# sfpp_conn.net
KiCad netlist of a schematic drawn in Altium Designer
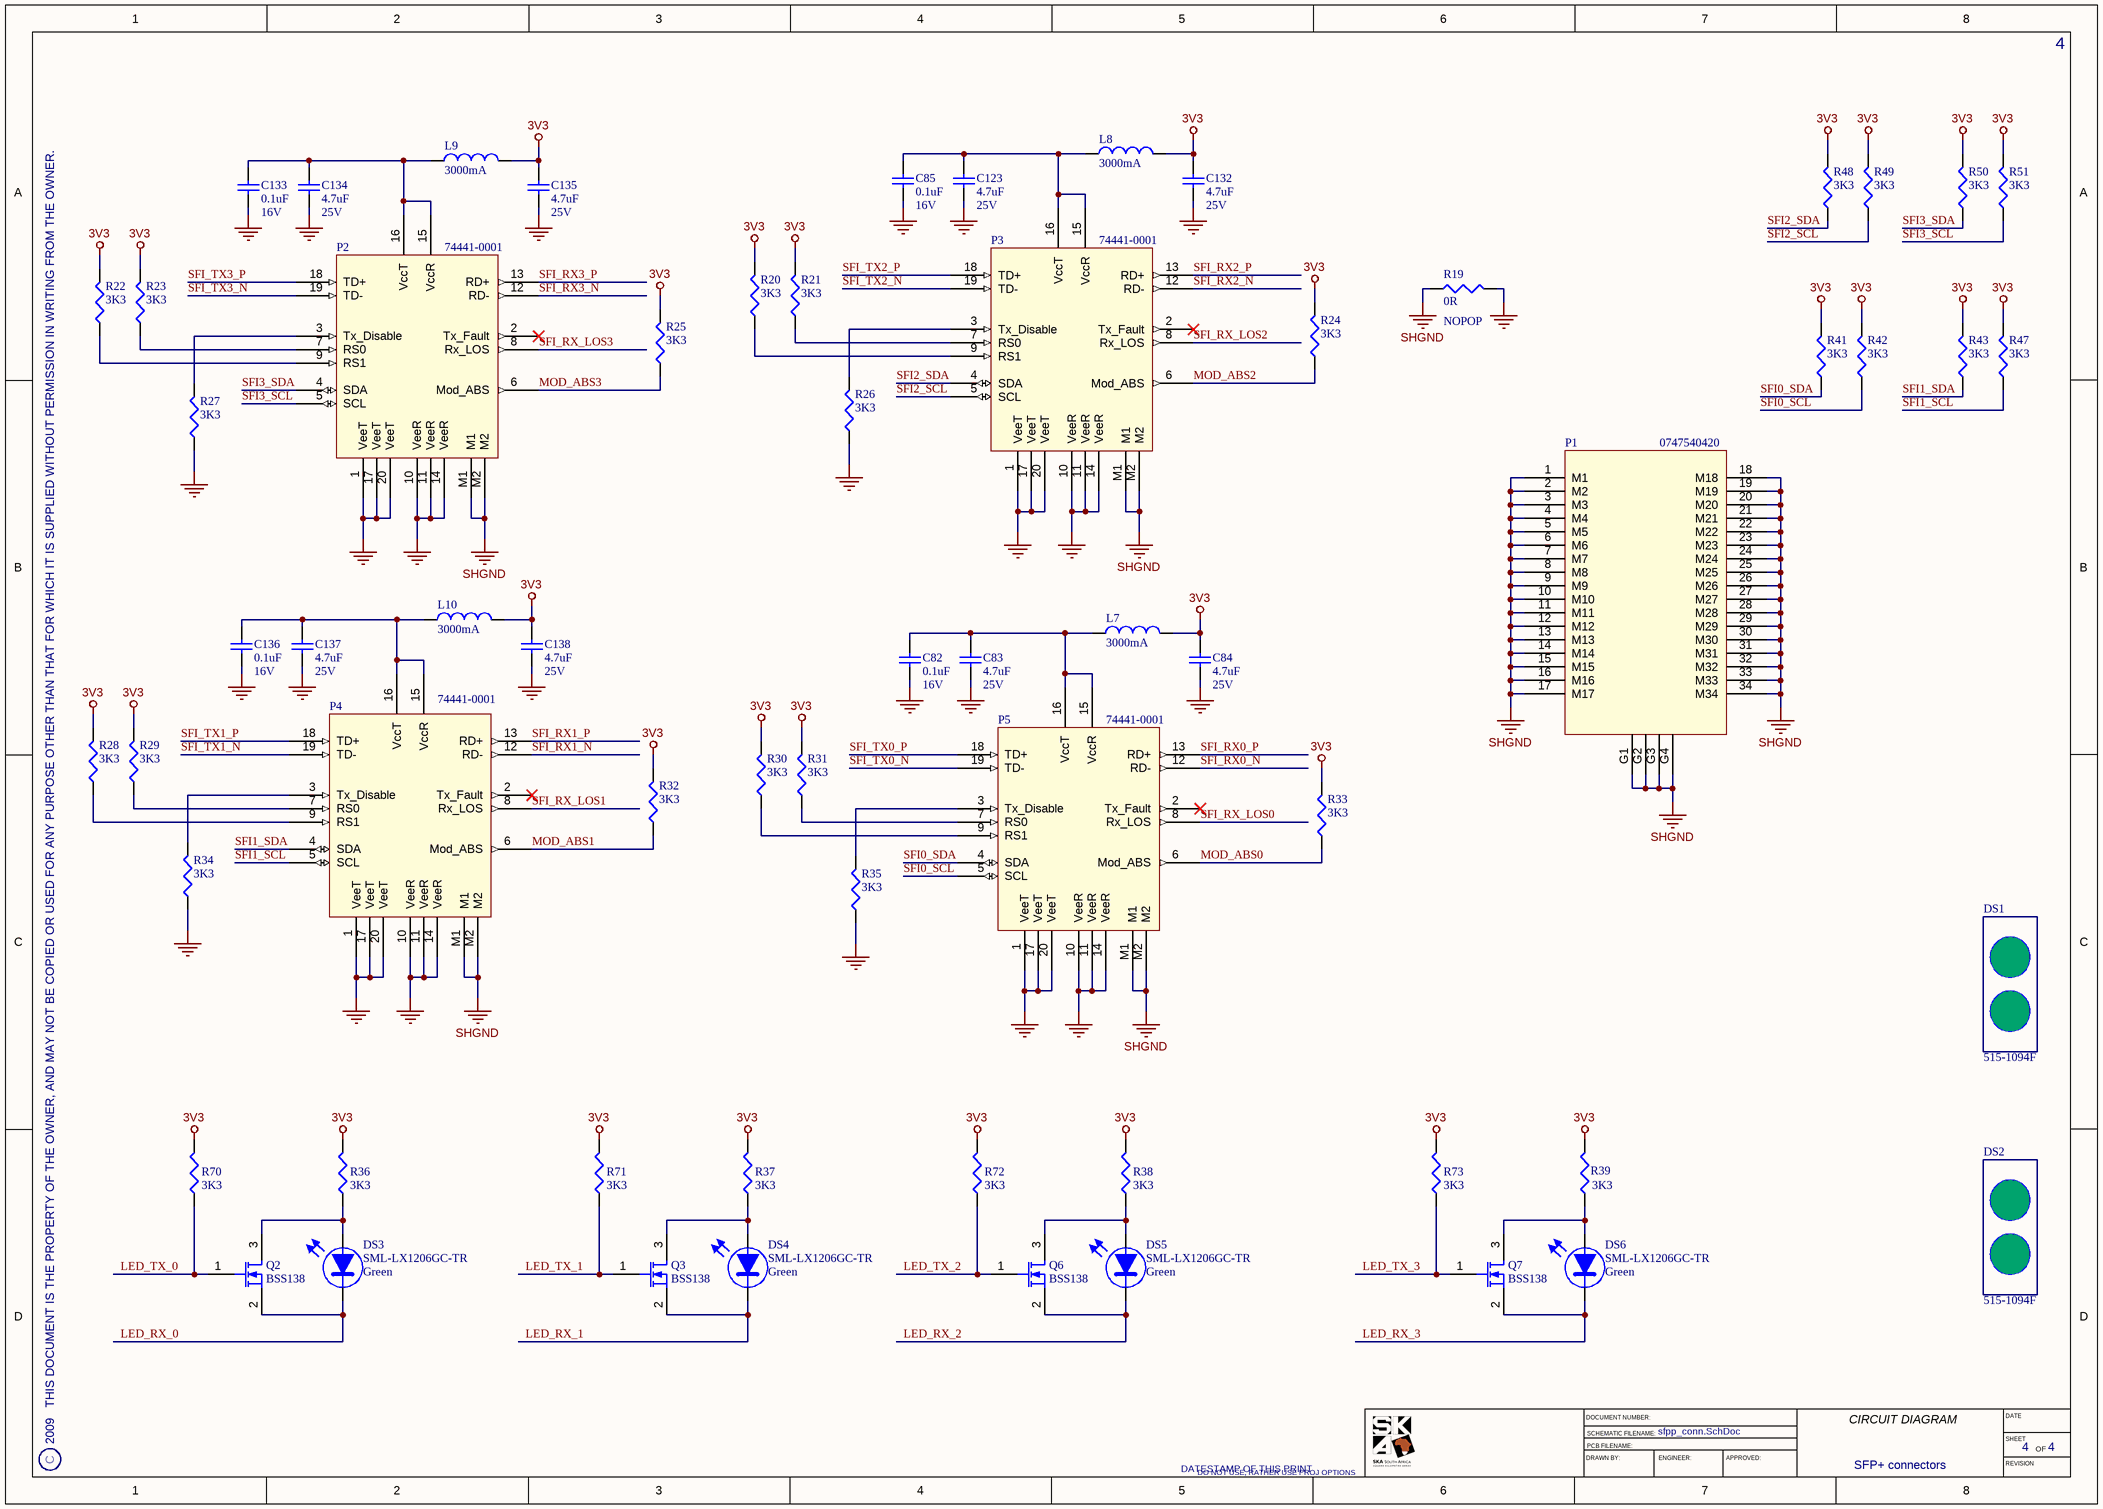
[diagram p0: sfpp_conn.SchDoc]

(export (version "E")
  (design (tool "Eeschema 10.0.6"))
  (components
    (comp (ref "C82")
      (value "0.1uF")
      (footprint "CAPC1005X60L")
      (description "0.1uF, Ceramic Capacitor")
      (fields
        (field (name "RATING") "16V")
        (field (name "MANUFACTURER") "VENKEL")
        (field (name "PARTNUM") "C0402X7R160-104KN")
      )
      (libsource (lib "altium_db") (part "CapStd"))
    )
    (comp (ref "C83")
      (value "4.7uF")
      (footprint "CAPC2012X127L")
      (description "4.7uF, Ceramic Capacitor")
      (fields
        (field (name "RATING") "25V")
        (field (name "MANUFACTURER") "MURATA")
        (field (name "PARTNUM") "GRM21BR61E475KA12K")
      )
      (libsource (lib "altium_db") (part "CapStd"))
    )
    (comp (ref "C84")
      (value "4.7uF")
      (footprint "CAPC2012X127L")
      (description "4.7uF, Ceramic Capacitor")
      (fields
        (field (name "RATING") "25V")
        (field (name "MANUFACTURER") "MURATA")
        (field (name "PARTNUM") "GRM21BR61E475KA12K")
      )
      (libsource (lib "altium_db") (part "CapStd"))
    )
    (comp (ref "C85")
      (value "0.1uF")
      (footprint "CAPC1005X60L")
      (description "0.1uF, Ceramic Capacitor")
      (fields
        (field (name "RATING") "16V")
        (field (name "MANUFACTURER") "VENKEL")
        (field (name "PARTNUM") "C0402X7R160-104KN")
      )
      (libsource (lib "altium_db") (part "CapStd"))
    )
    (comp (ref "C123")
      (value "4.7uF")
      (footprint "CAPC2012X127L")
      (description "4.7uF, Ceramic Capacitor")
      (fields
        (field (name "RATING") "25V")
        (field (name "MANUFACTURER") "MURATA")
        (field (name "PARTNUM") "GRM21BR61E475KA12K")
      )
      (libsource (lib "altium_db") (part "CapStd"))
    )
    (comp (ref "C132")
      (value "4.7uF")
      (footprint "CAPC2012X127L")
      (description "4.7uF, Ceramic Capacitor")
      (fields
        (field (name "RATING") "25V")
        (field (name "MANUFACTURER") "MURATA")
        (field (name "PARTNUM") "GRM21BR61E475KA12K")
      )
      (libsource (lib "altium_db") (part "CapStd"))
    )
    (comp (ref "C133")
      (value "0.1uF")
      (footprint "CAPC1005X60L")
      (description "0.1uF, Ceramic Capacitor")
      (fields
        (field (name "RATING") "16V")
        (field (name "MANUFACTURER") "VENKEL")
        (field (name "PARTNUM") "C0402X7R160-104KN")
      )
      (libsource (lib "altium_db") (part "CapStd"))
    )
    (comp (ref "C134")
      (value "4.7uF")
      (footprint "CAPC2012X127L")
      (description "4.7uF, Ceramic Capacitor")
      (fields
        (field (name "RATING") "25V")
        (field (name "MANUFACTURER") "MURATA")
        (field (name "PARTNUM") "GRM21BR61E475KA12K")
      )
      (libsource (lib "altium_db") (part "CapStd"))
    )
    (comp (ref "C135")
      (value "4.7uF")
      (footprint "CAPC2012X127L")
      (description "4.7uF, Ceramic Capacitor")
      (fields
        (field (name "RATING") "25V")
        (field (name "MANUFACTURER") "MURATA")
        (field (name "PARTNUM") "GRM21BR61E475KA12K")
      )
      (libsource (lib "altium_db") (part "CapStd"))
    )
    (comp (ref "C136")
      (value "0.1uF")
      (footprint "CAPC1005X60L")
      (description "0.1uF, Ceramic Capacitor")
      (fields
        (field (name "RATING") "16V")
        (field (name "MANUFACTURER") "VENKEL")
        (field (name "PARTNUM") "C0402X7R160-104KN")
      )
      (libsource (lib "altium_db") (part "CapStd"))
    )
    (comp (ref "C137")
      (value "4.7uF")
      (footprint "CAPC2012X127L")
      (description "4.7uF, Ceramic Capacitor")
      (fields
        (field (name "RATING") "25V")
        (field (name "MANUFACTURER") "MURATA")
        (field (name "PARTNUM") "GRM21BR61E475KA12K")
      )
      (libsource (lib "altium_db") (part "CapStd"))
    )
    (comp (ref "C138")
      (value "4.7uF")
      (footprint "CAPC2012X127L")
      (description "4.7uF, Ceramic Capacitor")
      (fields
        (field (name "RATING") "25V")
        (field (name "MANUFACTURER") "MURATA")
        (field (name "PARTNUM") "GRM21BR61E475KA12K")
      )
      (libsource (lib "altium_db") (part "CapStd"))
    )
    (comp (ref "DS1")
      (value "515-1094F")
      (footprint "DIALIGHT_515-1094F")
      (description "2-High, press-fit, 3mm round, light-pipe")
      (fields (field (name "MANUFACTURER") "Dialight"))
      (libsource (lib "altium_db") (part "LPIPE_2H"))
    )
    (comp (ref "DS2")
      (value "515-1094F")
      (footprint "DIALIGHT_515-1094F")
      (description "2-High, press-fit, 3mm round, light-pipe")
      (fields (field (name "MANUFACTURER") "Dialight"))
      (libsource (lib "altium_db") (part "LPIPE_2H"))
    )
    (comp (ref "DS3")
      (value "SML-LX1206GC-TR")
      (footprint "LEDC3216X120N")
      (description "Green, Surface mount, LED, 1206")
      (fields (field (name "COLOUR") "Green") (field (name "MANUFACTURER") "LUMEX"))
      (libsource (lib "altium_db") (part "LEDSTD"))
    )
    (comp (ref "DS4")
      (value "SML-LX1206GC-TR")
      (footprint "LEDC3216X120N")
      (description "Green, Surface mount, LED, 1206")
      (fields (field (name "COLOUR") "Green") (field (name "MANUFACTURER") "LUMEX"))
      (libsource (lib "altium_db") (part "LEDSTD"))
    )
    (comp (ref "DS5")
      (value "SML-LX1206GC-TR")
      (footprint "LEDC3216X120N")
      (description "Green, Surface mount, LED, 1206")
      (fields (field (name "COLOUR") "Green") (field (name "MANUFACTURER") "LUMEX"))
      (libsource (lib "altium_db") (part "LEDSTD"))
    )
    (comp (ref "DS6")
      (value "SML-LX1206GC-TR")
      (footprint "LEDC3216X120N")
      (description "Green, Surface mount, LED, 1206")
      (fields (field (name "COLOUR") "Green") (field (name "MANUFACTURER") "LUMEX"))
      (libsource (lib "altium_db") (part "LEDSTD"))
    )
    (comp (ref "L7")
      (value "120R")
      (footprint "INDC3216X130L")
      (description "120 Ohm, Chip Ferrite Brad")
      (fields
        (field (name "RATING") "3000mA")
        (field (name "MANUFACTURER") "Murata")
        (field (name "PARTNUM") "BLM31PG121SN1")
      )
      (libsource (lib "altium_db") (part "IndStd"))
    )
    (comp (ref "L8")
      (value "120R")
      (footprint "INDC3216X130L")
      (description "120 Ohm, Chip Ferrite Brad")
      (fields
        (field (name "RATING") "3000mA")
        (field (name "MANUFACTURER") "Murata")
        (field (name "PARTNUM") "BLM31PG121SN1")
      )
      (libsource (lib "altium_db") (part "IndStd"))
    )
    (comp (ref "L9")
      (value "120R")
      (footprint "INDC3216X130L")
      (description "120 Ohm, Chip Ferrite Brad")
      (fields
        (field (name "RATING") "3000mA")
        (field (name "MANUFACTURER") "Murata")
        (field (name "PARTNUM") "BLM31PG121SN1")
      )
      (libsource (lib "altium_db") (part "IndStd"))
    )
    (comp (ref "L10")
      (value "120R")
      (footprint "INDC3216X130L")
      (description "120 Ohm, Chip Ferrite Brad")
      (fields
        (field (name "RATING") "3000mA")
        (field (name "MANUFACTURER") "Murata")
        (field (name "PARTNUM") "BLM31PG121SN1")
      )
      (libsource (lib "altium_db") (part "IndStd"))
    )
    (comp (ref "P1")
      (value "0747540420")
      (footprint "MOLEX_0747540420")
      (description "SFP+ 1X4 Cage Assembly")
      (fields (field (name "PARTNUM") "0747540420") (field (name "MANUFACTURER") "Molex"))
      (libsource (lib "altium_db") (part "MOLEX_0747540420"))
    )
    (comp (ref "P2")
      (value "74441-0001")
      (footprint "MOLEX_74441-0001")
      (description "20 Circuit, 0.8mm pitch SFP+ host connector")
      (fields (field (name "PARTNUM") "74441-0001") (field (name "MANUFACTURER") "Molex"))
      (libsource (lib "altium_db") (part "MOLEX_74441-0001"))
    )
    (comp (ref "P3")
      (value "74441-0001")
      (footprint "MOLEX_74441-0001")
      (description "20 Circuit, 0.8mm pitch SFP+ host connector")
      (fields (field (name "PARTNUM") "74441-0001") (field (name "MANUFACTURER") "Molex"))
      (libsource (lib "altium_db") (part "MOLEX_74441-0001"))
    )
    (comp (ref "P4")
      (value "74441-0001")
      (footprint "MOLEX_74441-0001")
      (description "20 Circuit, 0.8mm pitch SFP+ host connector")
      (fields (field (name "PARTNUM") "74441-0001") (field (name "MANUFACTURER") "Molex"))
      (libsource (lib "altium_db") (part "MOLEX_74441-0001"))
    )
    (comp (ref "P5")
      (value "74441-0001")
      (footprint "MOLEX_74441-0001")
      (description "20 Circuit, 0.8mm pitch SFP+ host connector")
      (fields (field (name "PARTNUM") "74441-0001") (field (name "MANUFACTURER") "Molex"))
      (libsource (lib "altium_db") (part "MOLEX_74441-0001"))
    )
    (comp (ref "Q2")
      (value "BSS138")
      (footprint "SOT95P245X110-3N")
      (description "N-Channel Logic Level Enhancement Mode Field Effect Transistor")
      (fields (field (name "MANUFACTURER") "Fairchild Semiconductor"))
      (libsource (lib "Altium_DB") (part "BSS138"))
    )
    (comp (ref "Q3")
      (value "BSS138")
      (footprint "SOT95P245X110-3N")
      (description "N-Channel Logic Level Enhancement Mode Field Effect Transistor")
      (fields (field (name "MANUFACTURER") "Fairchild Semiconductor"))
      (libsource (lib "Altium_DB") (part "BSS138"))
    )
    (comp (ref "Q6")
      (value "BSS138")
      (footprint "SOT95P245X110-3N")
      (description "N-Channel Logic Level Enhancement Mode Field Effect Transistor")
      (fields (field (name "MANUFACTURER") "Fairchild Semiconductor"))
      (libsource (lib "Altium_DB") (part "BSS138"))
    )
    (comp (ref "Q7")
      (value "BSS138")
      (footprint "SOT95P245X110-3N")
      (description "N-Channel Logic Level Enhancement Mode Field Effect Transistor")
      (fields (field (name "MANUFACTURER") "Fairchild Semiconductor"))
      (libsource (lib "Altium_DB") (part "BSS138"))
    )
    (comp (ref "R19")
      (value "0R")
      (footprint "RESC1005X40L")
      (description "0R, 1.1mm x 0.5mm, Thick Film Resistor")
      (fields (field (name "MANUFACTURER") "ROYALOHM") (field (name "PARTNUM") "0402WG00000T1E"))
      (libsource (lib "altium_db") (part "ResStd"))
    )
    (comp (ref "R20")
      (value "3K3")
      (footprint "RESC1005X40L")
      (description "3K3, 1.1mm x 0.5mm, Thick Film Resistor")
      (fields (field (name "MANUFACTURER") "ROYALOHM") (field (name "PARTNUM") "0402WGJ0332T1E"))
      (libsource (lib "altium_db") (part "ResStd"))
    )
    (comp (ref "R21")
      (value "3K3")
      (footprint "RESC1005X40L")
      (description "3K3, 1.1mm x 0.5mm, Thick Film Resistor")
      (fields (field (name "MANUFACTURER") "ROYALOHM") (field (name "PARTNUM") "0402WGJ0332T1E"))
      (libsource (lib "altium_db") (part "ResStd"))
    )
    (comp (ref "R22")
      (value "3K3")
      (footprint "RESC1005X40L")
      (description "3K3, 1.1mm x 0.5mm, Thick Film Resistor")
      (fields (field (name "MANUFACTURER") "ROYALOHM") (field (name "PARTNUM") "0402WGJ0332T1E"))
      (libsource (lib "altium_db") (part "ResStd"))
    )
    (comp (ref "R23")
      (value "3K3")
      (footprint "RESC1005X40L")
      (description "3K3, 1.1mm x 0.5mm, Thick Film Resistor")
      (fields (field (name "MANUFACTURER") "ROYALOHM") (field (name "PARTNUM") "0402WGJ0332T1E"))
      (libsource (lib "altium_db") (part "ResStd"))
    )
    (comp (ref "R24")
      (value "3K3")
      (footprint "RESC1005X40L")
      (description "3K3, 1.1mm x 0.5mm, Thick Film Resistor")
      (fields (field (name "MANUFACTURER") "ROYALOHM") (field (name "PARTNUM") "0402WGJ0332T1E"))
      (libsource (lib "altium_db") (part "ResStd"))
    )
    (comp (ref "R25")
      (value "3K3")
      (footprint "RESC1005X40L")
      (description "3K3, 1.1mm x 0.5mm, Thick Film Resistor")
      (fields (field (name "MANUFACTURER") "ROYALOHM") (field (name "PARTNUM") "0402WGJ0332T1E"))
      (libsource (lib "altium_db") (part "ResStd"))
    )
    (comp (ref "R26")
      (value "3K3")
      (footprint "RESC1005X40L")
      (description "3K3, 1.1mm x 0.5mm, Thick Film Resistor")
      (fields (field (name "MANUFACTURER") "ROYALOHM") (field (name "PARTNUM") "0402WGJ0332T1E"))
      (libsource (lib "altium_db") (part "ResStd"))
    )
    (comp (ref "R27")
      (value "3K3")
      (footprint "RESC1005X40L")
      (description "3K3, 1.1mm x 0.5mm, Thick Film Resistor")
      (fields (field (name "MANUFACTURER") "ROYALOHM") (field (name "PARTNUM") "0402WGJ0332T1E"))
      (libsource (lib "altium_db") (part "ResStd"))
    )
    (comp (ref "R28")
      (value "3K3")
      (footprint "RESC1005X40L")
      (description "3K3, 1.1mm x 0.5mm, Thick Film Resistor")
      (fields (field (name "MANUFACTURER") "ROYALOHM") (field (name "PARTNUM") "0402WGJ0332T1E"))
      (libsource (lib "altium_db") (part "ResStd"))
    )
    (comp (ref "R29")
      (value "3K3")
      (footprint "RESC1005X40L")
      (description "3K3, 1.1mm x 0.5mm, Thick Film Resistor")
      (fields (field (name "MANUFACTURER") "ROYALOHM") (field (name "PARTNUM") "0402WGJ0332T1E"))
      (libsource (lib "altium_db") (part "ResStd"))
    )
    (comp (ref "R30")
      (value "3K3")
      (footprint "RESC1005X40L")
      (description "3K3, 1.1mm x 0.5mm, Thick Film Resistor")
      (fields (field (name "MANUFACTURER") "ROYALOHM") (field (name "PARTNUM") "0402WGJ0332T1E"))
      (libsource (lib "altium_db") (part "ResStd"))
    )
    (comp (ref "R31")
      (value "3K3")
      (footprint "RESC1005X40L")
      (description "3K3, 1.1mm x 0.5mm, Thick Film Resistor")
      (fields (field (name "MANUFACTURER") "ROYALOHM") (field (name "PARTNUM") "0402WGJ0332T1E"))
      (libsource (lib "altium_db") (part "ResStd"))
    )
    (comp (ref "R32")
      (value "3K3")
      (footprint "RESC1005X40L")
      (description "3K3, 1.1mm x 0.5mm, Thick Film Resistor")
      (fields (field (name "MANUFACTURER") "ROYALOHM") (field (name "PARTNUM") "0402WGJ0332T1E"))
      (libsource (lib "altium_db") (part "ResStd"))
    )
    (comp (ref "R33")
      (value "3K3")
      (footprint "RESC1005X40L")
      (description "3K3, 1.1mm x 0.5mm, Thick Film Resistor")
      (fields (field (name "MANUFACTURER") "ROYALOHM") (field (name "PARTNUM") "0402WGJ0332T1E"))
      (libsource (lib "altium_db") (part "ResStd"))
    )
    (comp (ref "R34")
      (value "3K3")
      (footprint "RESC1005X40L")
      (description "3K3, 1.1mm x 0.5mm, Thick Film Resistor")
      (fields (field (name "MANUFACTURER") "ROYALOHM") (field (name "PARTNUM") "0402WGJ0332T1E"))
      (libsource (lib "altium_db") (part "ResStd"))
    )
    (comp (ref "R35")
      (value "3K3")
      (footprint "RESC1005X40L")
      (description "3K3, 1.1mm x 0.5mm, Thick Film Resistor")
      (fields (field (name "MANUFACTURER") "ROYALOHM") (field (name "PARTNUM") "0402WGJ0332T1E"))
      (libsource (lib "altium_db") (part "ResStd"))
    )
    (comp (ref "R36")
      (value "3K3")
      (footprint "RESC1005X40L")
      (description "3K3, 1.1mm x 0.5mm, Thick Film Resistor")
      (fields (field (name "MANUFACTURER") "ROYALOHM") (field (name "PARTNUM") "0402WGJ0332T1E"))
      (libsource (lib "Altium_DB") (part "ResStd"))
    )
    (comp (ref "R37")
      (value "3K3")
      (footprint "RESC1005X40L")
      (description "3K3, 1.1mm x 0.5mm, Thick Film Resistor")
      (fields (field (name "MANUFACTURER") "ROYALOHM") (field (name "PARTNUM") "0402WGJ0332T1E"))
      (libsource (lib "Altium_DB") (part "ResStd"))
    )
    (comp (ref "R38")
      (value "3K3")
      (footprint "RESC1005X40L")
      (description "3K3, 1.1mm x 0.5mm, Thick Film Resistor")
      (fields (field (name "MANUFACTURER") "ROYALOHM") (field (name "PARTNUM") "0402WGJ0332T1E"))
      (libsource (lib "Altium_DB") (part "ResStd"))
    )
    (comp (ref "R39")
      (value "3K3")
      (footprint "RESC1005X40L")
      (description "3K3, 1.1mm x 0.5mm, Thick Film Resistor")
      (fields (field (name "MANUFACTURER") "ROYALOHM") (field (name "PARTNUM") "0402WGJ0332T1E"))
      (libsource (lib "Altium_DB") (part "ResStd"))
    )
    (comp (ref "R41")
      (value "3K3")
      (footprint "RESC1005X40L")
      (description "3K3, 1.1mm x 0.5mm, Thick Film Resistor")
      (fields (field (name "MANUFACTURER") "ROYALOHM") (field (name "PARTNUM") "0402WGJ0332T1E"))
      (libsource (lib "altium_db") (part "ResStd"))
    )
    (comp (ref "R42")
      (value "3K3")
      (footprint "RESC1005X40L")
      (description "3K3, 1.1mm x 0.5mm, Thick Film Resistor")
      (fields (field (name "MANUFACTURER") "ROYALOHM") (field (name "PARTNUM") "0402WGJ0332T1E"))
      (libsource (lib "altium_db") (part "ResStd"))
    )
    (comp (ref "R43")
      (value "3K3")
      (footprint "RESC1005X40L")
      (description "3K3, 1.1mm x 0.5mm, Thick Film Resistor")
      (fields (field (name "MANUFACTURER") "ROYALOHM") (field (name "PARTNUM") "0402WGJ0332T1E"))
      (libsource (lib "altium_db") (part "ResStd"))
    )
    (comp (ref "R47")
      (value "3K3")
      (footprint "RESC1005X40L")
      (description "3K3, 1.1mm x 0.5mm, Thick Film Resistor")
      (fields (field (name "MANUFACTURER") "ROYALOHM") (field (name "PARTNUM") "0402WGJ0332T1E"))
      (libsource (lib "altium_db") (part "ResStd"))
    )
    (comp (ref "R48")
      (value "3K3")
      (footprint "RESC1005X40L")
      (description "3K3, 1.1mm x 0.5mm, Thick Film Resistor")
      (fields (field (name "MANUFACTURER") "ROYALOHM") (field (name "PARTNUM") "0402WGJ0332T1E"))
      (libsource (lib "altium_db") (part "ResStd"))
    )
    (comp (ref "R49")
      (value "3K3")
      (footprint "RESC1005X40L")
      (description "3K3, 1.1mm x 0.5mm, Thick Film Resistor")
      (fields (field (name "MANUFACTURER") "ROYALOHM") (field (name "PARTNUM") "0402WGJ0332T1E"))
      (libsource (lib "altium_db") (part "ResStd"))
    )
    (comp (ref "R50")
      (value "3K3")
      (footprint "RESC1005X40L")
      (description "3K3, 1.1mm x 0.5mm, Thick Film Resistor")
      (fields (field (name "MANUFACTURER") "ROYALOHM") (field (name "PARTNUM") "0402WGJ0332T1E"))
      (libsource (lib "altium_db") (part "ResStd"))
    )
    (comp (ref "R51")
      (value "3K3")
      (footprint "RESC1005X40L")
      (description "3K3, 1.1mm x 0.5mm, Thick Film Resistor")
      (fields (field (name "MANUFACTURER") "ROYALOHM") (field (name "PARTNUM") "0402WGJ0332T1E"))
      (libsource (lib "altium_db") (part "ResStd"))
    )
    (comp (ref "R70")
      (value "3K3")
      (footprint "RESC1005X40L")
      (description "3K3, 1.1mm x 0.5mm, Thick Film Resistor")
      (fields (field (name "MANUFACTURER") "ROYALOHM") (field (name "PARTNUM") "0402WGJ0332T1E"))
      (libsource (lib "Altium_DB") (part "ResStd"))
    )
    (comp (ref "R71")
      (value "3K3")
      (footprint "RESC1005X40L")
      (description "3K3, 1.1mm x 0.5mm, Thick Film Resistor")
      (fields (field (name "MANUFACTURER") "ROYALOHM") (field (name "PARTNUM") "0402WGJ0332T1E"))
      (libsource (lib "Altium_DB") (part "ResStd"))
    )
    (comp (ref "R72")
      (value "3K3")
      (footprint "RESC1005X40L")
      (description "3K3, 1.1mm x 0.5mm, Thick Film Resistor")
      (fields (field (name "MANUFACTURER") "ROYALOHM") (field (name "PARTNUM") "0402WGJ0332T1E"))
      (libsource (lib "Altium_DB") (part "ResStd"))
    )
    (comp (ref "R73")
      (value "3K3")
      (footprint "RESC1005X40L")
      (description "3K3, 1.1mm x 0.5mm, Thick Film Resistor")
      (fields (field (name "MANUFACTURER") "ROYALOHM") (field (name "PARTNUM") "0402WGJ0332T1E"))
      (libsource (lib "Altium_DB") (part "ResStd"))
    )
  )
  (nets
    (net (code "1") (name "/LED_RX_0") (class "Default")
      (node (ref "DS3") (pin "1") (pinfunction "K_1") (pintype "passive"))
      (node (ref "Q2") (pin "2") (pinfunction "S_2") (pintype "passive"))
    )
    (net (code "2") (name "/LED_RX_1") (class "Default")
      (node (ref "DS4") (pin "1") (pinfunction "K_1") (pintype "passive"))
      (node (ref "Q3") (pin "2") (pinfunction "S_2") (pintype "passive"))
    )
    (net (code "3") (name "/LED_RX_2") (class "Default")
      (node (ref "DS5") (pin "1") (pinfunction "K_1") (pintype "passive"))
      (node (ref "Q6") (pin "2") (pinfunction "S_2") (pintype "passive"))
    )
    (net (code "4") (name "/LED_RX_3") (class "Default")
      (node (ref "DS6") (pin "1") (pinfunction "K_1") (pintype "passive"))
      (node (ref "Q7") (pin "2") (pinfunction "S_2") (pintype "passive"))
    )
    (net (code "5") (name "/LED_TX_0") (class "Default")
      (node (ref "Q2") (pin "1") (pinfunction "G_1") (pintype "passive"))
      (node (ref "R70") (pin "1") (pinfunction "1_1") (pintype "passive"))
    )
    (net (code "6") (name "/LED_TX_1") (class "Default")
      (node (ref "Q3") (pin "1") (pinfunction "G_1") (pintype "passive"))
      (node (ref "R71") (pin "1") (pinfunction "1_1") (pintype "passive"))
    )
    (net (code "7") (name "/LED_TX_2") (class "Default")
      (node (ref "Q6") (pin "1") (pinfunction "G_1") (pintype "passive"))
      (node (ref "R72") (pin "1") (pinfunction "1_1") (pintype "passive"))
    )
    (net (code "8") (name "/LED_TX_3") (class "Default")
      (node (ref "Q7") (pin "1") (pinfunction "G_1") (pintype "passive"))
      (node (ref "R73") (pin "1") (pinfunction "1_1") (pintype "passive"))
    )
    (net (code "9") (name "/MOD_ABS0") (class "Default")
      (node (ref "P5") (pin "6") (pinfunction "Mod_ABS_6") (pintype "output"))
      (node (ref "R33") (pin "1") (pinfunction "1_1") (pintype "passive"))
    )
    (net (code "10") (name "/MOD_ABS1") (class "Default")
      (node (ref "P4") (pin "6") (pinfunction "Mod_ABS_6") (pintype "output"))
      (node (ref "R32") (pin "1") (pinfunction "1_1") (pintype "passive"))
    )
    (net (code "11") (name "/MOD_ABS2") (class "Default")
      (node (ref "P3") (pin "6") (pinfunction "Mod_ABS_6") (pintype "output"))
      (node (ref "R24") (pin "1") (pinfunction "1_1") (pintype "passive"))
    )
    (net (code "12") (name "/MOD_ABS3") (class "Default")
      (node (ref "P2") (pin "6") (pinfunction "Mod_ABS_6") (pintype "output"))
      (node (ref "R25") (pin "1") (pinfunction "1_1") (pintype "passive"))
    )
    (net (code "13") (name "/SFI0_SCL") (class "Default")
      (node (ref "P5") (pin "5") (pinfunction "SCL_5") (pintype "bidirectional"))
      (node (ref "R42") (pin "1") (pinfunction "1_1") (pintype "passive"))
    )
    (net (code "14") (name "/SFI0_SDA") (class "Default")
      (node (ref "P5") (pin "4") (pinfunction "SDA_4") (pintype "bidirectional"))
      (node (ref "R41") (pin "1") (pinfunction "1_1") (pintype "passive"))
    )
    (net (code "15") (name "/SFI1_SCL") (class "Default")
      (node (ref "P4") (pin "5") (pinfunction "SCL_5") (pintype "bidirectional"))
      (node (ref "R47") (pin "1") (pinfunction "1_1") (pintype "passive"))
    )
    (net (code "16") (name "/SFI1_SDA") (class "Default")
      (node (ref "P4") (pin "4") (pinfunction "SDA_4") (pintype "bidirectional"))
      (node (ref "R43") (pin "1") (pinfunction "1_1") (pintype "passive"))
    )
    (net (code "17") (name "/SFI2_SCL") (class "Default")
      (node (ref "P3") (pin "5") (pinfunction "SCL_5") (pintype "bidirectional"))
      (node (ref "R49") (pin "1") (pinfunction "1_1") (pintype "passive"))
    )
    (net (code "18") (name "/SFI2_SDA") (class "Default")
      (node (ref "P3") (pin "4") (pinfunction "SDA_4") (pintype "bidirectional"))
      (node (ref "R48") (pin "1") (pinfunction "1_1") (pintype "passive"))
    )
    (net (code "19") (name "/SFI3_SCL") (class "Default")
      (node (ref "P2") (pin "5") (pinfunction "SCL_5") (pintype "bidirectional"))
      (node (ref "R51") (pin "1") (pinfunction "1_1") (pintype "passive"))
    )
    (net (code "20") (name "/SFI3_SDA") (class "Default")
      (node (ref "P2") (pin "4") (pinfunction "SDA_4") (pintype "bidirectional"))
      (node (ref "R50") (pin "1") (pinfunction "1_1") (pintype "passive"))
    )
    (net (code "21") (name "/SFI_RX0_N") (class "Default")
      (node (ref "P5") (pin "12") (pinfunction "RD-_12") (pintype "output"))
    )
    (net (code "22") (name "/SFI_RX0_P") (class "Default")
      (node (ref "P5") (pin "13") (pinfunction "RD+_13") (pintype "output"))
    )
    (net (code "23") (name "/SFI_RX1_N") (class "Default")
      (node (ref "P4") (pin "12") (pinfunction "RD-_12") (pintype "output"))
    )
    (net (code "24") (name "/SFI_RX1_P") (class "Default")
      (node (ref "P4") (pin "13") (pinfunction "RD+_13") (pintype "output"))
    )
    (net (code "25") (name "/SFI_RX2_N") (class "Default")
      (node (ref "P3") (pin "12") (pinfunction "RD-_12") (pintype "output"))
    )
    (net (code "26") (name "/SFI_RX2_P") (class "Default")
      (node (ref "P3") (pin "13") (pinfunction "RD+_13") (pintype "output"))
    )
    (net (code "27") (name "/SFI_RX3_N") (class "Default")
      (node (ref "P2") (pin "12") (pinfunction "RD-_12") (pintype "output"))
    )
    (net (code "28") (name "/SFI_RX3_P") (class "Default")
      (node (ref "P2") (pin "13") (pinfunction "RD+_13") (pintype "output"))
    )
    (net (code "29") (name "/SFI_RX_LOS0") (class "Default")
      (node (ref "P5") (pin "8") (pinfunction "Rx_LOS_8") (pintype "output"))
    )
    (net (code "30") (name "/SFI_RX_LOS1") (class "Default")
      (node (ref "P4") (pin "8") (pinfunction "Rx_LOS_8") (pintype "output"))
    )
    (net (code "31") (name "/SFI_RX_LOS2") (class "Default")
      (node (ref "P3") (pin "8") (pinfunction "Rx_LOS_8") (pintype "output"))
    )
    (net (code "32") (name "/SFI_RX_LOS3") (class "Default")
      (node (ref "P2") (pin "8") (pinfunction "Rx_LOS_8") (pintype "output"))
    )
    (net (code "33") (name "/SFI_TX0_N") (class "Default")
      (node (ref "P5") (pin "19") (pinfunction "TD-_19") (pintype "input"))
    )
    (net (code "34") (name "/SFI_TX0_P") (class "Default")
      (node (ref "P5") (pin "18") (pinfunction "TD+_18") (pintype "input"))
    )
    (net (code "35") (name "/SFI_TX1_N") (class "Default")
      (node (ref "P4") (pin "19") (pinfunction "TD-_19") (pintype "input"))
    )
    (net (code "36") (name "/SFI_TX1_P") (class "Default")
      (node (ref "P4") (pin "18") (pinfunction "TD+_18") (pintype "input"))
    )
    (net (code "37") (name "/SFI_TX2_N") (class "Default")
      (node (ref "P3") (pin "19") (pinfunction "TD-_19") (pintype "input"))
    )
    (net (code "38") (name "/SFI_TX2_P") (class "Default")
      (node (ref "P3") (pin "18") (pinfunction "TD+_18") (pintype "input"))
    )
    (net (code "39") (name "/SFI_TX3_N") (class "Default")
      (node (ref "P2") (pin "19") (pinfunction "TD-_19") (pintype "input"))
    )
    (net (code "40") (name "/SFI_TX3_P") (class "Default")
      (node (ref "P2") (pin "18") (pinfunction "TD+_18") (pintype "input"))
    )
    (net (code "41") (name "3V3") (class "Default")
      (node (ref "C132") (pin "2") (pinfunction "2_2") (pintype "passive"))
      (node (ref "C135") (pin "2") (pinfunction "2_2") (pintype "passive"))
      (node (ref "C138") (pin "2") (pinfunction "2_2") (pintype "passive"))
      (node (ref "C84") (pin "2") (pinfunction "2_2") (pintype "passive"))
      (node (ref "L10") (pin "2") (pinfunction "2_2") (pintype "passive"))
      (node (ref "L7") (pin "2") (pinfunction "2_2") (pintype "passive"))
      (node (ref "L8") (pin "2") (pinfunction "2_2") (pintype "passive"))
      (node (ref "L9") (pin "2") (pinfunction "2_2") (pintype "passive"))
      (node (ref "R20") (pin "2") (pinfunction "2_2") (pintype "passive"))
      (node (ref "R21") (pin "2") (pinfunction "2_2") (pintype "passive"))
      (node (ref "R22") (pin "2") (pinfunction "2_2") (pintype "passive"))
      (node (ref "R23") (pin "2") (pinfunction "2_2") (pintype "passive"))
      (node (ref "R24") (pin "2") (pinfunction "2_2") (pintype "passive"))
      (node (ref "R25") (pin "2") (pinfunction "2_2") (pintype "passive"))
      (node (ref "R28") (pin "2") (pinfunction "2_2") (pintype "passive"))
      (node (ref "R29") (pin "2") (pinfunction "2_2") (pintype "passive"))
      (node (ref "R30") (pin "2") (pinfunction "2_2") (pintype "passive"))
      (node (ref "R31") (pin "2") (pinfunction "2_2") (pintype "passive"))
      (node (ref "R32") (pin "2") (pinfunction "2_2") (pintype "passive"))
      (node (ref "R33") (pin "2") (pinfunction "2_2") (pintype "passive"))
      (node (ref "R36") (pin "2") (pinfunction "2_2") (pintype "passive"))
      (node (ref "R37") (pin "2") (pinfunction "2_2") (pintype "passive"))
      (node (ref "R38") (pin "2") (pinfunction "2_2") (pintype "passive"))
      (node (ref "R39") (pin "2") (pinfunction "2_2") (pintype "passive"))
      (node (ref "R41") (pin "2") (pinfunction "2_2") (pintype "passive"))
      (node (ref "R42") (pin "2") (pinfunction "2_2") (pintype "passive"))
      (node (ref "R43") (pin "2") (pinfunction "2_2") (pintype "passive"))
      (node (ref "R47") (pin "2") (pinfunction "2_2") (pintype "passive"))
      (node (ref "R48") (pin "2") (pinfunction "2_2") (pintype "passive"))
      (node (ref "R49") (pin "2") (pinfunction "2_2") (pintype "passive"))
      (node (ref "R50") (pin "2") (pinfunction "2_2") (pintype "passive"))
      (node (ref "R51") (pin "2") (pinfunction "2_2") (pintype "passive"))
      (node (ref "R70") (pin "2") (pinfunction "2_2") (pintype "passive"))
      (node (ref "R71") (pin "2") (pinfunction "2_2") (pintype "passive"))
      (node (ref "R72") (pin "2") (pinfunction "2_2") (pintype "passive"))
      (node (ref "R73") (pin "2") (pinfunction "2_2") (pintype "passive"))
    )
    (net (code "42") (name "GND") (class "Default")
      (node (ref "C123") (pin "1") (pinfunction "1_1") (pintype "passive"))
      (node (ref "C132") (pin "1") (pinfunction "1_1") (pintype "passive"))
      (node (ref "C133") (pin "1") (pinfunction "1_1") (pintype "passive"))
      (node (ref "C134") (pin "1") (pinfunction "1_1") (pintype "passive"))
      (node (ref "C135") (pin "1") (pinfunction "1_1") (pintype "passive"))
      (node (ref "C136") (pin "1") (pinfunction "1_1") (pintype "passive"))
      (node (ref "C137") (pin "1") (pinfunction "1_1") (pintype "passive"))
      (node (ref "C138") (pin "1") (pinfunction "1_1") (pintype "passive"))
      (node (ref "C82") (pin "1") (pinfunction "1_1") (pintype "passive"))
      (node (ref "C83") (pin "1") (pinfunction "1_1") (pintype "passive"))
      (node (ref "C84") (pin "1") (pinfunction "1_1") (pintype "passive"))
      (node (ref "C85") (pin "1") (pinfunction "1_1") (pintype "passive"))
      (node (ref "P2") (pin "1") (pinfunction "VeeT_1") (pintype "power_in"))
      (node (ref "P2") (pin "10") (pinfunction "VeeR_10") (pintype "power_in"))
      (node (ref "P2") (pin "11") (pinfunction "VeeR_11") (pintype "power_in"))
      (node (ref "P2") (pin "14") (pinfunction "VeeR_14") (pintype "power_in"))
      (node (ref "P2") (pin "17") (pinfunction "VeeT_17") (pintype "power_in"))
      (node (ref "P2") (pin "20") (pinfunction "VeeT_20") (pintype "power_in"))
      (node (ref "P3") (pin "1") (pinfunction "VeeT_1") (pintype "power_in"))
      (node (ref "P3") (pin "10") (pinfunction "VeeR_10") (pintype "power_in"))
      (node (ref "P3") (pin "11") (pinfunction "VeeR_11") (pintype "power_in"))
      (node (ref "P3") (pin "14") (pinfunction "VeeR_14") (pintype "power_in"))
      (node (ref "P3") (pin "17") (pinfunction "VeeT_17") (pintype "power_in"))
      (node (ref "P3") (pin "20") (pinfunction "VeeT_20") (pintype "power_in"))
      (node (ref "P4") (pin "1") (pinfunction "VeeT_1") (pintype "power_in"))
      (node (ref "P4") (pin "10") (pinfunction "VeeR_10") (pintype "power_in"))
      (node (ref "P4") (pin "11") (pinfunction "VeeR_11") (pintype "power_in"))
      (node (ref "P4") (pin "14") (pinfunction "VeeR_14") (pintype "power_in"))
      (node (ref "P4") (pin "17") (pinfunction "VeeT_17") (pintype "power_in"))
      (node (ref "P4") (pin "20") (pinfunction "VeeT_20") (pintype "power_in"))
      (node (ref "P5") (pin "1") (pinfunction "VeeT_1") (pintype "power_in"))
      (node (ref "P5") (pin "10") (pinfunction "VeeR_10") (pintype "power_in"))
      (node (ref "P5") (pin "11") (pinfunction "VeeR_11") (pintype "power_in"))
      (node (ref "P5") (pin "14") (pinfunction "VeeR_14") (pintype "power_in"))
      (node (ref "P5") (pin "17") (pinfunction "VeeT_17") (pintype "power_in"))
      (node (ref "P5") (pin "20") (pinfunction "VeeT_20") (pintype "power_in"))
      (node (ref "R19") (pin "2") (pinfunction "2_2") (pintype "passive"))
      (node (ref "R26") (pin "1") (pinfunction "1_1") (pintype "passive"))
      (node (ref "R27") (pin "1") (pinfunction "1_1") (pintype "passive"))
      (node (ref "R34") (pin "1") (pinfunction "1_1") (pintype "passive"))
      (node (ref "R35") (pin "1") (pinfunction "1_1") (pintype "passive"))
    )
    (net (code "43") (name "Net-(DS3-A)") (class "Default")
      (node (ref "DS3") (pin "2") (pinfunction "A_2") (pintype "passive"))
      (node (ref "Q2") (pin "3") (pinfunction "D_3") (pintype "passive"))
      (node (ref "R36") (pin "1") (pinfunction "1_1") (pintype "passive"))
    )
    (net (code "44") (name "Net-(DS4-A)") (class "Default")
      (node (ref "DS4") (pin "2") (pinfunction "A_2") (pintype "passive"))
      (node (ref "Q3") (pin "3") (pinfunction "D_3") (pintype "passive"))
      (node (ref "R37") (pin "1") (pinfunction "1_1") (pintype "passive"))
    )
    (net (code "45") (name "Net-(DS5-A)") (class "Default")
      (node (ref "DS5") (pin "2") (pinfunction "A_2") (pintype "passive"))
      (node (ref "Q6") (pin "3") (pinfunction "D_3") (pintype "passive"))
      (node (ref "R38") (pin "1") (pinfunction "1_1") (pintype "passive"))
    )
    (net (code "46") (name "Net-(DS6-A)") (class "Default")
      (node (ref "DS6") (pin "2") (pinfunction "A_2") (pintype "passive"))
      (node (ref "Q7") (pin "3") (pinfunction "D_3") (pintype "passive"))
      (node (ref "R39") (pin "1") (pinfunction "1_1") (pintype "passive"))
    )
    (net (code "47") (name "Net-(P2-RS0)") (class "Default")
      (node (ref "P2") (pin "7") (pinfunction "RS0_7") (pintype "input"))
      (node (ref "R23") (pin "1") (pinfunction "1_1") (pintype "passive"))
    )
    (net (code "48") (name "Net-(P2-RS1)") (class "Default")
      (node (ref "P2") (pin "9") (pinfunction "RS1_9") (pintype "input"))
      (node (ref "R22") (pin "1") (pinfunction "1_1") (pintype "passive"))
    )
    (net (code "49") (name "Net-(P2-Tx_Disable)") (class "Default")
      (node (ref "P2") (pin "3") (pinfunction "Tx_Disable_3") (pintype "input"))
      (node (ref "R27") (pin "2") (pinfunction "2_2") (pintype "passive"))
    )
    (net (code "50") (name "Net-(P2-VccR)") (class "Default")
      (node (ref "C133") (pin "2") (pinfunction "2_2") (pintype "passive"))
      (node (ref "C134") (pin "2") (pinfunction "2_2") (pintype "passive"))
      (node (ref "L9") (pin "1") (pinfunction "1_1") (pintype "passive"))
      (node (ref "P2") (pin "15") (pinfunction "VccR_15") (pintype "power_in"))
      (node (ref "P2") (pin "16") (pinfunction "VccT_16") (pintype "power_in"))
    )
    (net (code "51") (name "Net-(P3-RS0)") (class "Default")
      (node (ref "P3") (pin "7") (pinfunction "RS0_7") (pintype "input"))
      (node (ref "R21") (pin "1") (pinfunction "1_1") (pintype "passive"))
    )
    (net (code "52") (name "Net-(P3-RS1)") (class "Default")
      (node (ref "P3") (pin "9") (pinfunction "RS1_9") (pintype "input"))
      (node (ref "R20") (pin "1") (pinfunction "1_1") (pintype "passive"))
    )
    (net (code "53") (name "Net-(P3-Tx_Disable)") (class "Default")
      (node (ref "P3") (pin "3") (pinfunction "Tx_Disable_3") (pintype "input"))
      (node (ref "R26") (pin "2") (pinfunction "2_2") (pintype "passive"))
    )
    (net (code "54") (name "Net-(P3-VccR)") (class "Default")
      (node (ref "C123") (pin "2") (pinfunction "2_2") (pintype "passive"))
      (node (ref "C85") (pin "2") (pinfunction "2_2") (pintype "passive"))
      (node (ref "L8") (pin "1") (pinfunction "1_1") (pintype "passive"))
      (node (ref "P3") (pin "15") (pinfunction "VccR_15") (pintype "power_in"))
      (node (ref "P3") (pin "16") (pinfunction "VccT_16") (pintype "power_in"))
    )
    (net (code "55") (name "Net-(P4-RS0)") (class "Default")
      (node (ref "P4") (pin "7") (pinfunction "RS0_7") (pintype "input"))
      (node (ref "R29") (pin "1") (pinfunction "1_1") (pintype "passive"))
    )
    (net (code "56") (name "Net-(P4-RS1)") (class "Default")
      (node (ref "P4") (pin "9") (pinfunction "RS1_9") (pintype "input"))
      (node (ref "R28") (pin "1") (pinfunction "1_1") (pintype "passive"))
    )
    (net (code "57") (name "Net-(P4-Tx_Disable)") (class "Default")
      (node (ref "P4") (pin "3") (pinfunction "Tx_Disable_3") (pintype "input"))
      (node (ref "R34") (pin "2") (pinfunction "2_2") (pintype "passive"))
    )
    (net (code "58") (name "Net-(P4-VccR)") (class "Default")
      (node (ref "C136") (pin "2") (pinfunction "2_2") (pintype "passive"))
      (node (ref "C137") (pin "2") (pinfunction "2_2") (pintype "passive"))
      (node (ref "L10") (pin "1") (pinfunction "1_1") (pintype "passive"))
      (node (ref "P4") (pin "15") (pinfunction "VccR_15") (pintype "power_in"))
      (node (ref "P4") (pin "16") (pinfunction "VccT_16") (pintype "power_in"))
    )
    (net (code "59") (name "Net-(P5-RS0)") (class "Default")
      (node (ref "P5") (pin "7") (pinfunction "RS0_7") (pintype "input"))
      (node (ref "R31") (pin "1") (pinfunction "1_1") (pintype "passive"))
    )
    (net (code "60") (name "Net-(P5-RS1)") (class "Default")
      (node (ref "P5") (pin "9") (pinfunction "RS1_9") (pintype "input"))
      (node (ref "R30") (pin "1") (pinfunction "1_1") (pintype "passive"))
    )
    (net (code "61") (name "Net-(P5-Tx_Disable)") (class "Default")
      (node (ref "P5") (pin "3") (pinfunction "Tx_Disable_3") (pintype "input"))
      (node (ref "R35") (pin "2") (pinfunction "2_2") (pintype "passive"))
    )
    (net (code "62") (name "Net-(P5-VccR)") (class "Default")
      (node (ref "C82") (pin "2") (pinfunction "2_2") (pintype "passive"))
      (node (ref "C83") (pin "2") (pinfunction "2_2") (pintype "passive"))
      (node (ref "L7") (pin "1") (pinfunction "1_1") (pintype "passive"))
      (node (ref "P5") (pin "15") (pinfunction "VccR_15") (pintype "power_in"))
      (node (ref "P5") (pin "16") (pinfunction "VccT_16") (pintype "power_in"))
    )
    (net (code "63") (name "SHGND") (class "Default")
      (node (ref "P1") (pin "1") (pinfunction "M1_1") (pintype "power_in"))
      (node (ref "P1") (pin "10") (pinfunction "M10_10") (pintype "power_in"))
      (node (ref "P1") (pin "11") (pinfunction "M11_11") (pintype "power_in"))
      (node (ref "P1") (pin "12") (pinfunction "M12_12") (pintype "power_in"))
      (node (ref "P1") (pin "13") (pinfunction "M13_13") (pintype "power_in"))
      (node (ref "P1") (pin "14") (pinfunction "M14_14") (pintype "power_in"))
      (node (ref "P1") (pin "15") (pinfunction "M15_15") (pintype "power_in"))
      (node (ref "P1") (pin "16") (pinfunction "M16_16") (pintype "power_in"))
      (node (ref "P1") (pin "17") (pinfunction "M17_17") (pintype "power_in"))
      (node (ref "P1") (pin "18") (pinfunction "M18_18") (pintype "power_in"))
      (node (ref "P1") (pin "19") (pinfunction "M19_19") (pintype "power_in"))
      (node (ref "P1") (pin "2") (pinfunction "M2_2") (pintype "power_in"))
      (node (ref "P1") (pin "20") (pinfunction "M20_20") (pintype "power_in"))
      (node (ref "P1") (pin "21") (pinfunction "M21_21") (pintype "power_in"))
      (node (ref "P1") (pin "22") (pinfunction "M22_22") (pintype "power_in"))
      (node (ref "P1") (pin "23") (pinfunction "M23_23") (pintype "power_in"))
      (node (ref "P1") (pin "24") (pinfunction "M24_24") (pintype "power_in"))
      (node (ref "P1") (pin "25") (pinfunction "M25_25") (pintype "power_in"))
      (node (ref "P1") (pin "26") (pinfunction "M26_26") (pintype "power_in"))
      (node (ref "P1") (pin "27") (pinfunction "M27_27") (pintype "power_in"))
      (node (ref "P1") (pin "28") (pinfunction "M28_28") (pintype "power_in"))
      (node (ref "P1") (pin "29") (pinfunction "M29_29") (pintype "power_in"))
      (node (ref "P1") (pin "3") (pinfunction "M3_3") (pintype "power_in"))
      (node (ref "P1") (pin "30") (pinfunction "M30_30") (pintype "power_in"))
      (node (ref "P1") (pin "31") (pinfunction "M31_31") (pintype "power_in"))
      (node (ref "P1") (pin "32") (pinfunction "M32_32") (pintype "power_in"))
      (node (ref "P1") (pin "33") (pinfunction "M33_33") (pintype "power_in"))
      (node (ref "P1") (pin "34") (pinfunction "M34_34") (pintype "power_in"))
      (node (ref "P1") (pin "4") (pinfunction "M4_4") (pintype "power_in"))
      (node (ref "P1") (pin "5") (pinfunction "M5_5") (pintype "power_in"))
      (node (ref "P1") (pin "6") (pinfunction "M6_6") (pintype "power_in"))
      (node (ref "P1") (pin "7") (pinfunction "M7_7") (pintype "power_in"))
      (node (ref "P1") (pin "8") (pinfunction "M8_8") (pintype "power_in"))
      (node (ref "P1") (pin "9") (pinfunction "M9_9") (pintype "power_in"))
      (node (ref "P1") (pin "G1") (pinfunction "G1_G1") (pintype "power_in"))
      (node (ref "P1") (pin "G2") (pinfunction "G2_G2") (pintype "power_in"))
      (node (ref "P1") (pin "G3") (pinfunction "G3_G3") (pintype "power_in"))
      (node (ref "P1") (pin "G4") (pinfunction "G4_G4") (pintype "power_in"))
      (node (ref "P2") (pin "M1") (pinfunction "M1_M1") (pintype "passive"))
      (node (ref "P2") (pin "M2") (pinfunction "M2_M2") (pintype "passive"))
      (node (ref "P3") (pin "M1") (pinfunction "M1_M1") (pintype "passive"))
      (node (ref "P3") (pin "M2") (pinfunction "M2_M2") (pintype "passive"))
      (node (ref "P4") (pin "M1") (pinfunction "M1_M1") (pintype "passive"))
      (node (ref "P4") (pin "M2") (pinfunction "M2_M2") (pintype "passive"))
      (node (ref "P5") (pin "M1") (pinfunction "M1_M1") (pintype "passive"))
      (node (ref "P5") (pin "M2") (pinfunction "M2_M2") (pintype "passive"))
      (node (ref "R19") (pin "1") (pinfunction "1_1") (pintype "passive"))
    )
    (net (code "64") (name "unconnected-(P2-Tx_Fault-Pad2)") (class "Default")
      (node (ref "P2") (pin "2") (pinfunction "Tx_Fault_2") (pintype "output+no_connect"))
    )
    (net (code "65") (name "unconnected-(P3-Tx_Fault-Pad2)") (class "Default")
      (node (ref "P3") (pin "2") (pinfunction "Tx_Fault_2") (pintype "output+no_connect"))
    )
    (net (code "66") (name "unconnected-(P4-Tx_Fault-Pad2)") (class "Default")
      (node (ref "P4") (pin "2") (pinfunction "Tx_Fault_2") (pintype "output+no_connect"))
    )
    (net (code "67") (name "unconnected-(P5-Tx_Fault-Pad2)") (class "Default")
      (node (ref "P5") (pin "2") (pinfunction "Tx_Fault_2") (pintype "output+no_connect"))
    )
  )
)
